# WallLightRemote_V1_0_Power.net
KiCad netlist of a schematic drawn in Altium Designer
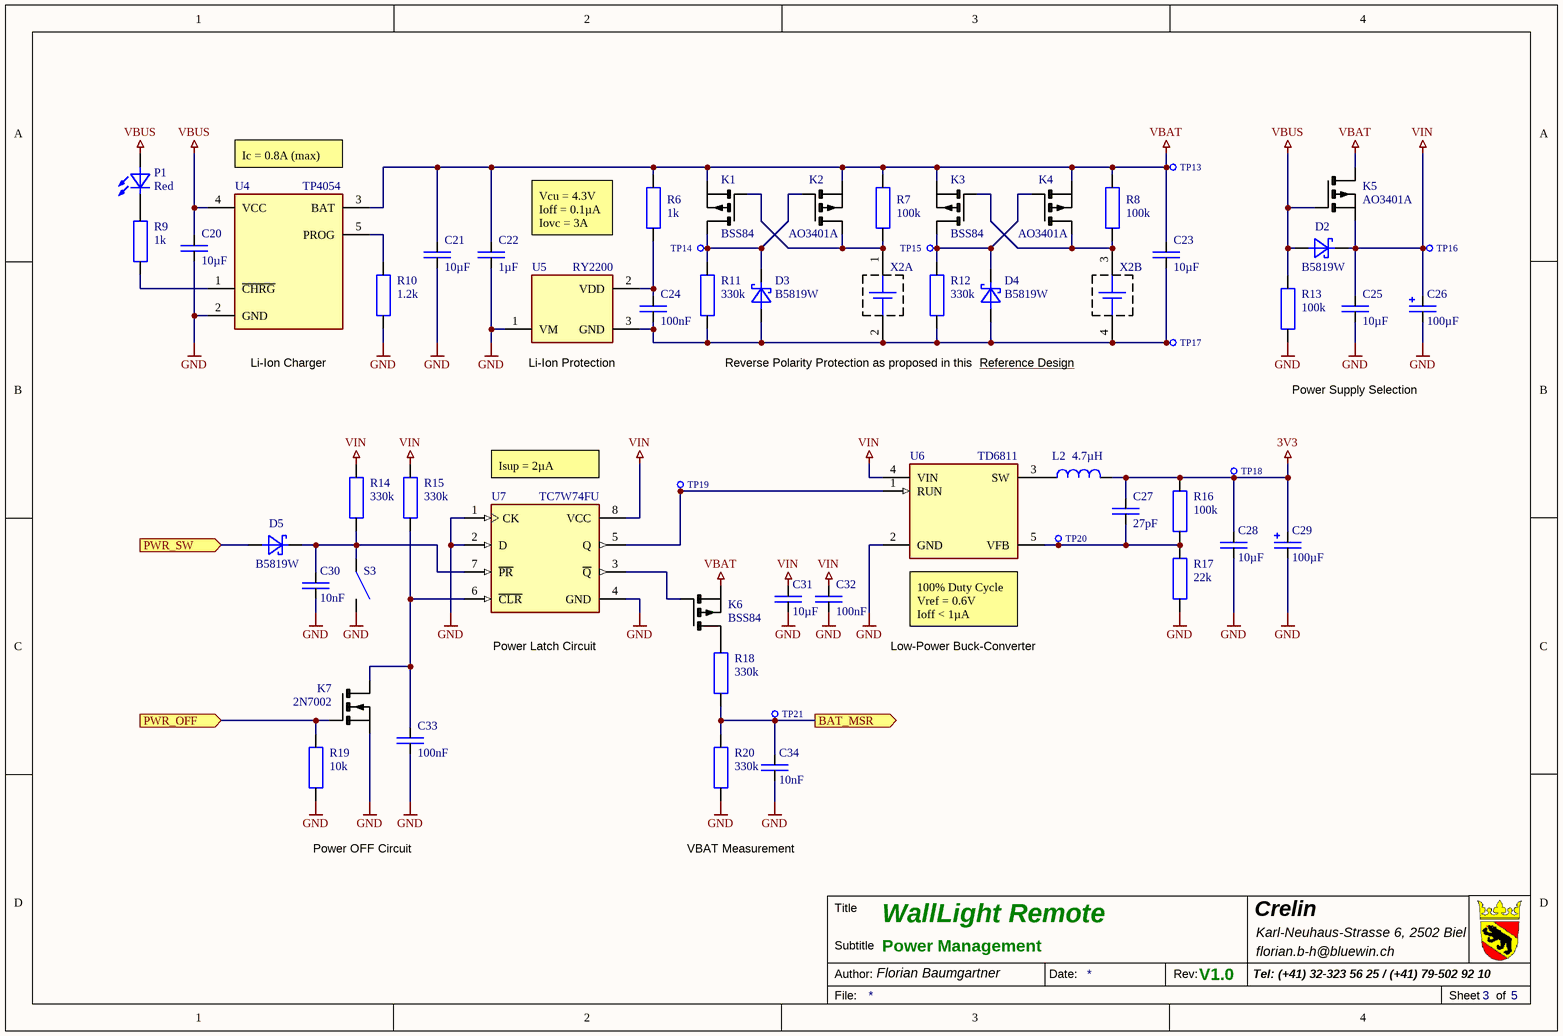
[diagram p0: WallLightRemote_V1.0_Power.SchDoc]

(export (version "E")
  (design (tool "Eeschema 10.0.6"))
  (components
    (comp (ref "C20")
      (value "10µF")
      (footprint "SMD Keramikkondensator 1206")
      (description "SMD Ceramic Capacitor E6")
      (libsource (lib "Ceramic Capacitors-E6") (part "E6 - 10uF"))
    )
    (comp (ref "C21")
      (value "10µF")
      (footprint "SMD Keramikkondensator 1206")
      (description "SMD Ceramic Capacitor E6")
      (libsource (lib "Ceramic Capacitors-E6") (part "E6 - 10uF"))
    )
    (comp (ref "C22")
      (value "1µF")
      (footprint "SMD Keramikkondensator 0603")
      (description "CAP-MK")
      (libsource (lib "AudioAmp") (part "C-CAPACITOR"))
    )
    (comp (ref "C23")
      (value "10µF")
      (footprint "SMD Keramikkondensator 1206")
      (description "SMD Ceramic Capacitor E6")
      (libsource (lib "Ceramic Capacitors-E6") (part "E6 - 10uF"))
    )
    (comp (ref "C24")
      (value "100nF")
      (footprint "SMD Keramikkondensator 0603")
      (description "SMD Ceramic Capacitor E6")
      (libsource (lib "Ceramic Capacitors-E6") (part "E6 - 100nF"))
    )
    (comp (ref "C25")
      (value "10µF")
      (footprint "SMD Keramikkondensator 1206")
      (description "SMD Ceramic Capacitor E6")
      (libsource (lib "Ceramic Capacitors-E6") (part "E6 - 10uF"))
    )
    (comp (ref "C26")
      (value "100µF")
      (footprint "SMD Tantalkondensator 1210 +")
      (description "CAP-Elko")
      (libsource (lib "TFS Integrated Library") (part "C-ELCAP"))
    )
    (comp (ref "C27")
      (value "27pF")
      (footprint "SMD Keramikkondensator 0603")
      (description "CAP-MK")
      (libsource (lib "AudioAmp") (part "C-CAPACITOR"))
    )
    (comp (ref "C28")
      (value "10µF")
      (footprint "SMD Keramikkondensator 1206")
      (description "CAP-MK")
      (libsource (lib "AudioAmp") (part "C-CAPACITOR"))
    )
    (comp (ref "C29")
      (value "100µF")
      (footprint "SMD Tantalkondensator 1210 +")
      (description "CAP-Elko")
      (libsource (lib "TFS Integrated Library") (part "C-ELCAP"))
    )
    (comp (ref "C30")
      (value "10nF")
      (footprint "SMD Keramikkondensator 0603")
      (description "CAP-MK")
      (libsource (lib "AudioAmp") (part "C-CAPACITOR"))
    )
    (comp (ref "C31")
      (value "10µF")
      (footprint "SMD Keramikkondensator 1206")
      (description "CAP-MK")
      (libsource (lib "AudioAmp") (part "C-CAPACITOR"))
    )
    (comp (ref "C32")
      (value "100nF")
      (footprint "SMD Keramikkondensator 0603")
      (description "SMD Ceramic Capacitor E6")
      (libsource (lib "Ceramic Capacitors-E6") (part "E6 - 100nF"))
    )
    (comp (ref "C33")
      (value "100nF")
      (footprint "SMD Keramikkondensator 0603")
      (description "SMD Ceramic Capacitor E6")
      (libsource (lib "Ceramic Capacitors-E6") (part "E6 - 100nF"))
    )
    (comp (ref "C34")
      (value "10nF")
      (footprint "SMD Keramikkondensator 0603")
      (description "CAP-MK")
      (libsource (lib "AudioAmp") (part "C-CAPACITOR"))
    )
    (comp (ref "D2")
      (value "B5819W")
      (footprint "SMD Diode SOD-123")
      (description "S-DIODE")
      (libsource (lib "TFS Integrated Library") (part "R-DIODE{colon}SCHKY"))
    )
    (comp (ref "D3")
      (value "B5819W")
      (footprint "SMD Diode SOD-123")
      (description "S-DIODE")
      (libsource (lib "TFS Integrated Library") (part "R-DIODE{colon}SCHKY"))
    )
    (comp (ref "D4")
      (value "B5819W")
      (footprint "SMD Diode SOD-123")
      (description "S-DIODE")
      (libsource (lib "TFS Integrated Library") (part "R-DIODE{colon}SCHKY"))
    )
    (comp (ref "D5")
      (value "B5819W")
      (footprint "SMD Diode SOD-123")
      (description "S-DIODE")
      (libsource (lib "TFS Integrated Library") (part "R-DIODE{colon}SCHKY"))
    )
    (comp (ref "K1")
      (value "BSS84")
      (footprint "SMD MOSFET SOT-23")
      (description "MOSFET P-Channel")
      (libsource (lib "") (part "K-FET{colon}PIGE_2"))
    )
    (comp (ref "K2")
      (value "AO3401A")
      (footprint "SMD MOSFET SOT-23")
      (description "MOSFET P-Channel")
      (libsource (lib "VLD-Monitor_V1.0") (part "K-FET{colon}PIGE"))
    )
    (comp (ref "K3")
      (value "BSS84")
      (footprint "SMD MOSFET SOT-23")
      (description "MOSFET P-Channel")
      (libsource (lib "") (part "K-FET{colon}PIGE_2"))
    )
    (comp (ref "K4")
      (value "AO3401A")
      (footprint "SMD MOSFET SOT-23")
      (description "MOSFET P-Channel")
      (libsource (lib "VLD-Monitor_V1.0") (part "K-FET{colon}PIGE"))
    )
    (comp (ref "K5")
      (value "AO3401A")
      (footprint "SMD MOSFET SOT-23")
      (description "MOSFET P-Channel")
      (libsource (lib "") (part "K-FET{colon}PIGE_1"))
    )
    (comp (ref "K6")
      (value "BSS84")
      (footprint "SMD MOSFET SOT-23")
      (description "MOSFET P-Channel")
      (libsource (lib "VLD-Monitor_V1.0") (part "K-FET{colon}PIGE"))
    )
    (comp (ref "K7")
      (value "2N7002")
      (footprint "SMD MOSFET SOT-23")
      (description "MOSFET N-Channel")
      (libsource (lib "Nixie-Test") (part "K-FET{colon}NIGE"))
    )
    (comp (ref "L2")
      (value "4.7µH")
      (footprint "SMD Inductor 3.2x2.5x1.7")
      (description "Shielded Power Inductor")
      (libsource (lib "Nixie-Test") (part "L-COIL"))
    )
    (comp (ref "P1")
      (value "Red")
      (footprint "SMD LED 0603")
      (description "LED (als Lampe E / alt H)")
      (libsource (lib "TFS Integrated Library") (part "P-LED"))
    )
    (comp (ref "R6")
      (value "1k")
      (footprint "SMD Widerstand 0603")
      (description "RES (E=Heizwiderstand B=Messwandler)")
      (libsource (lib "") (part "R-RESISTOR_1"))
    )
    (comp (ref "R7")
      (value "100k")
      (footprint "SMD Widerstand 0603")
      (description "RES (E=Heizwiderstand B=Messwandler)")
      (libsource (lib "TFS Integrated Library") (part "R-RESISTOR"))
    )
    (comp (ref "R8")
      (value "100k")
      (footprint "SMD Widerstand 0603")
      (description "RES (E=Heizwiderstand B=Messwandler)")
      (libsource (lib "TFS Integrated Library") (part "R-RESISTOR"))
    )
    (comp (ref "R9")
      (value "1k")
      (footprint "SMD Widerstand 0603")
      (description "RES (E=Heizwiderstand B=Messwandler)")
      (libsource (lib "") (part "R-RESISTOR_2"))
    )
    (comp (ref "R10")
      (value "1.2k")
      (footprint "SMD Widerstand 0603")
      (description "RES (E=Heizwiderstand B=Messwandler)")
      (libsource (lib "TFS Integrated Library") (part "R-RESISTOR"))
    )
    (comp (ref "R11")
      (value "330k")
      (footprint "SMD Widerstand 0603")
      (description "RES (E=Heizwiderstand B=Messwandler)")
      (libsource (lib "TFS Integrated Library") (part "R-RESISTOR"))
    )
    (comp (ref "R12")
      (value "330k")
      (footprint "SMD Widerstand 0603")
      (description "RES (E=Heizwiderstand B=Messwandler)")
      (libsource (lib "TFS Integrated Library") (part "R-RESISTOR"))
    )
    (comp (ref "R13")
      (value "100k")
      (footprint "SMD Widerstand 0603")
      (description "RES (E=Heizwiderstand B=Messwandler)")
      (libsource (lib "TFS Integrated Library") (part "R-RESISTOR"))
    )
    (comp (ref "R14")
      (value "330k")
      (footprint "SMD Widerstand 0603")
      (description "RES (E=Heizwiderstand B=Messwandler)")
      (libsource (lib "TFS Integrated Library") (part "R-RESISTOR"))
    )
    (comp (ref "R15")
      (value "330k")
      (footprint "SMD Widerstand 0603")
      (description "RES (E=Heizwiderstand B=Messwandler)")
      (libsource (lib "TFS Integrated Library") (part "R-RESISTOR"))
    )
    (comp (ref "R16")
      (value "100k")
      (footprint "SMD Widerstand 0603")
      (description "RES (E=Heizwiderstand B=Messwandler)")
      (libsource (lib "TFS Integrated Library") (part "R-RESISTOR"))
    )
    (comp (ref "R17")
      (value "22k")
      (footprint "SMD Widerstand 0603")
      (description "RES (E=Heizwiderstand B=Messwandler)")
      (libsource (lib "") (part "R-RESISTOR_1"))
    )
    (comp (ref "R18")
      (value "330k")
      (footprint "SMD Widerstand 0603")
      (description "RES (E=Heizwiderstand B=Messwandler)")
      (libsource (lib "TFS Integrated Library") (part "R-RESISTOR"))
    )
    (comp (ref "R19")
      (value "10k")
      (footprint "SMD Widerstand 0603")
      (description "RES (E=Heizwiderstand B=Messwandler)")
      (libsource (lib "") (part "R-RESISTOR_1"))
    )
    (comp (ref "R20")
      (value "330k")
      (footprint "SMD Widerstand 0603")
      (description "RES (E=Heizwiderstand B=Messwandler)")
      (libsource (lib "TFS Integrated Library") (part "R-RESISTOR"))
    )
    (comp (ref "S3")
      (value "SMD-Button")
      (footprint "SMD Button 6.5x6.0x2.5")
      (description "Button SPST")
      (libsource (lib "Switches") (part "Button 3mmx2.5mm"))
    )
    (comp (ref "TP13")
      (value "X-TP")
      (footprint "SMD Testpunkt Ø1mm")
      (description "Testpunkt")
      (libsource (lib "VLD-Monitor_V1.0") (part "X-TP"))
    )
    (comp (ref "TP14")
      (value "X-TP")
      (footprint "SMD Testpunkt Ø1mm")
      (description "Testpunkt")
      (libsource (lib "VLD-Monitor_V1.0") (part "X-TP"))
    )
    (comp (ref "TP15")
      (value "X-TP")
      (footprint "SMD Testpunkt Ø1mm")
      (description "Testpunkt")
      (libsource (lib "VLD-Monitor_V1.0") (part "X-TP"))
    )
    (comp (ref "TP16")
      (value "X-TP")
      (footprint "SMD Testpunkt Ø1mm")
      (description "Testpunkt")
      (libsource (lib "VLD-Monitor_V1.0") (part "X-TP"))
    )
    (comp (ref "TP17")
      (value "X-TP")
      (footprint "SMD Testpunkt Ø1mm")
      (description "Testpunkt")
      (libsource (lib "VLD-Monitor_V1.0") (part "X-TP"))
    )
    (comp (ref "TP18")
      (value "X-TP")
      (footprint "SMD Testpunkt Ø1mm")
      (description "Testpunkt")
      (libsource (lib "VLD-Monitor_V1.0") (part "X-TP"))
    )
    (comp (ref "TP19")
      (value "X-TP")
      (footprint "SMD Testpunkt Ø1mm")
      (description "Testpunkt")
      (libsource (lib "VLD-Monitor_V1.0") (part "X-TP"))
    )
    (comp (ref "TP20")
      (value "X-TP")
      (footprint "SMD Testpunkt Ø1mm")
      (description "Testpunkt")
      (libsource (lib "VLD-Monitor_V1.0") (part "X-TP"))
    )
    (comp (ref "TP21")
      (value "X-TP")
      (footprint "SMD Testpunkt Ø1mm")
      (description "Testpunkt")
      (libsource (lib "VLD-Monitor_V1.0") (part "X-TP"))
    )
    (comp (ref "U4")
      (value "TP4054")
      (footprint "SMD IC SOT-23-5")
      (description "Standalone Linear Li-Ion Battery Charger")
      (libsource (lib "Velotour_2022") (part "U-TP4054"))
    )
    (comp (ref "U5")
      (value "RY2200")
      (footprint "SMD IC SOT-23-3")
      (description "One Cell Li-ion and Li-poly Battery Protection IC")
      (libsource (lib "Velotour_2022") (part "U-RY2200"))
    )
    (comp (ref "U6")
      (value "TD6811")
      (footprint "SMD IC SOT-23-5")
      (description "1.5MHz 1.2A Synchronous Step-Down Converter")
      (libsource (lib "Velotour_2022") (part "U-TD6811"))
    )
    (comp (ref "U7")
      (value "TC7W74FU")
      (footprint "SMD IC TSSOP-8")
      (description "Low-Power D-Flip-Flop with Preset & Clear")
      (libsource (lib "Velotour_2022") (part "U-TC7W74FU"))
    )
    (comp (ref "X2")
      (value "18650 Dual Battery Holder")
      (footprint "SMD Battery-Holder (1048P)")
      (libsource (lib "Velotour_2022") (part "X-18650_Dual-Holder"))
    )
  )
  (nets
    (net (code "1") (name "/BAT_MSR") (class "Default")
      (node (ref "C34") (pin "2") (pinfunction "2_2") (pintype "passive"))
      (node (ref "R18") (pin "1") (pinfunction "1_1") (pintype "passive"))
      (node (ref "R20") (pin "2") (pinfunction "2_2") (pintype "passive"))
      (node (ref "TP21") (pin "1") (pinfunction "1_1") (pintype "passive"))
    )
    (net (code "2") (name "/PWR_OFF") (class "Default")
      (node (ref "K7") (pin "G") (pinfunction "G_G") (pintype "passive"))
      (node (ref "R19") (pin "2") (pinfunction "2_2") (pintype "passive"))
    )
    (net (code "3") (name "/PWR_SW") (class "Default")
      (node (ref "D5") (pin "A") (pinfunction "A_A") (pintype "passive"))
    )
    (net (code "4") (name "3V3") (class "Default")
      (node (ref "C27") (pin "1") (pinfunction "1_1") (pintype "passive"))
      (node (ref "C28") (pin "2") (pinfunction "2_2") (pintype "passive"))
      (node (ref "C29") (pin "P") (pinfunction "+_P") (pintype "passive"))
      (node (ref "L2") (pin "2") (pinfunction "2_2") (pintype "passive"))
      (node (ref "R16") (pin "2") (pinfunction "2_2") (pintype "passive"))
      (node (ref "TP18") (pin "1") (pinfunction "1_1") (pintype "passive"))
    )
    (net (code "5") (name "GND") (class "Default")
      (node (ref "C20") (pin "1") (pinfunction "1_1") (pintype "passive"))
      (node (ref "C21") (pin "1") (pinfunction "1_1") (pintype "passive"))
      (node (ref "C22") (pin "1") (pinfunction "1_1") (pintype "passive"))
      (node (ref "C25") (pin "1") (pinfunction "1_1") (pintype "passive"))
      (node (ref "C26") (pin "M") (pinfunction "-_M") (pintype "passive"))
      (node (ref "C28") (pin "1") (pinfunction "1_1") (pintype "passive"))
      (node (ref "C29") (pin "M") (pinfunction "-_M") (pintype "passive"))
      (node (ref "C30") (pin "1") (pinfunction "1_1") (pintype "passive"))
      (node (ref "C31") (pin "1") (pinfunction "1_1") (pintype "passive"))
      (node (ref "C32") (pin "1") (pinfunction "1_1") (pintype "passive"))
      (node (ref "C33") (pin "1") (pinfunction "1_1") (pintype "passive"))
      (node (ref "C34") (pin "1") (pinfunction "1_1") (pintype "passive"))
      (node (ref "K7") (pin "S") (pinfunction "S_S") (pintype "passive"))
      (node (ref "R10") (pin "1") (pinfunction "1_1") (pintype "passive"))
      (node (ref "R13") (pin "1") (pinfunction "1_1") (pintype "passive"))
      (node (ref "R17") (pin "1") (pinfunction "1_1") (pintype "passive"))
      (node (ref "R19") (pin "1") (pinfunction "1_1") (pintype "passive"))
      (node (ref "R20") (pin "1") (pinfunction "1_1") (pintype "passive"))
      (node (ref "S3") (pin "2") (pinfunction "2_2") (pintype "passive"))
      (node (ref "U4") (pin "2") (pinfunction "GND_2") (pintype "power_in"))
      (node (ref "U5") (pin "1") (pinfunction "VM_1") (pintype "power_in"))
      (node (ref "U6") (pin "2") (pinfunction "GND_2") (pintype "power_in"))
      (node (ref "U7") (pin "1") (pinfunction "CK_1") (pintype "input"))
      (node (ref "U7") (pin "2") (pinfunction "D_2") (pintype "input"))
      (node (ref "U7") (pin "4") (pinfunction "GND_4") (pintype "power_in"))
    )
    (net (code "6") (name "Net-(D3-PadK)") (class "Default")
      (node (ref "D3") (pin "K") (pinfunction "K_K") (pintype "passive"))
      (node (ref "K1") (pin "D") (pinfunction "D_D") (pintype "passive"))
      (node (ref "K2") (pin "G") (pinfunction "G_G") (pintype "passive"))
      (node (ref "R11") (pin "2") (pinfunction "2_2") (pintype "passive"))
      (node (ref "TP14") (pin "1") (pinfunction "1_1") (pintype "passive"))
    )
    (net (code "7") (name "Net-(D4-PadK)") (class "Default")
      (node (ref "D4") (pin "K") (pinfunction "K_K") (pintype "passive"))
      (node (ref "K3") (pin "D") (pinfunction "D_D") (pintype "passive"))
      (node (ref "K4") (pin "G") (pinfunction "G_G") (pintype "passive"))
      (node (ref "R12") (pin "2") (pinfunction "2_2") (pintype "passive"))
      (node (ref "TP15") (pin "1") (pinfunction "1_1") (pintype "passive"))
    )
    (net (code "8") (name "Net-(K6-PadD)") (class "Default")
      (node (ref "K6") (pin "D") (pinfunction "D_D") (pintype "passive"))
      (node (ref "R18") (pin "2") (pinfunction "2_2") (pintype "passive"))
    )
    (net (code "9") (name "Net-(P1-PadK)") (class "Default")
      (node (ref "P1") (pin "K") (pinfunction "K_K") (pintype "passive"))
      (node (ref "R9") (pin "1") (pinfunction "1_1") (pintype "passive"))
    )
    (net (code "10") (name "Net-(U4-PROG)") (class "Default")
      (node (ref "R10") (pin "2") (pinfunction "2_2") (pintype "passive"))
      (node (ref "U4") (pin "5") (pinfunction "PROG_5") (pintype "passive"))
    )
    (net (code "11") (name "Net-(U4-~{CHRG})") (class "Default")
      (node (ref "R9") (pin "2") (pinfunction "2_2") (pintype "passive"))
      (node (ref "U4") (pin "1") (pinfunction "~{CHRG}_1") (pintype "open_collector"))
    )
    (net (code "12") (name "Net-(U5-GND)") (class "Default")
      (node (ref "C23") (pin "1") (pinfunction "1_1") (pintype "passive"))
      (node (ref "C24") (pin "1") (pinfunction "1_1") (pintype "passive"))
      (node (ref "D3") (pin "A") (pinfunction "A_A") (pintype "passive"))
      (node (ref "D4") (pin "A") (pinfunction "A_A") (pintype "passive"))
      (node (ref "R11") (pin "1") (pinfunction "1_1") (pintype "passive"))
      (node (ref "R12") (pin "1") (pinfunction "1_1") (pintype "passive"))
      (node (ref "TP17") (pin "1") (pinfunction "1_1") (pintype "passive"))
      (node (ref "U5") (pin "3") (pinfunction "GND_3") (pintype "power_in"))
      (node (ref "X2") (pin "2") (pinfunction "B1N_2") (pintype "passive"))
      (node (ref "X2") (pin "4") (pinfunction "B2N_4") (pintype "passive"))
    )
    (net (code "13") (name "Net-(U5-VDD)") (class "Default")
      (node (ref "C24") (pin "2") (pinfunction "2_2") (pintype "passive"))
      (node (ref "R6") (pin "1") (pinfunction "1_1") (pintype "passive"))
      (node (ref "U5") (pin "2") (pinfunction "VDD_2") (pintype "power_in"))
    )
    (net (code "14") (name "Net-(U6-RUN)") (class "Default")
      (node (ref "TP19") (pin "1") (pinfunction "1_1") (pintype "passive"))
      (node (ref "U6") (pin "1") (pinfunction "RUN_1") (pintype "input"))
      (node (ref "U7") (pin "5") (pinfunction "Q_5") (pintype "output"))
    )
    (net (code "15") (name "Net-(U6-SW)") (class "Default")
      (node (ref "L2") (pin "1") (pinfunction "1_1") (pintype "passive"))
      (node (ref "U6") (pin "3") (pinfunction "SW_3") (pintype "passive"))
    )
    (net (code "16") (name "Net-(U6-VFB)") (class "Default")
      (node (ref "C27") (pin "2") (pinfunction "2_2") (pintype "passive"))
      (node (ref "R16") (pin "1") (pinfunction "1_1") (pintype "passive"))
      (node (ref "R17") (pin "2") (pinfunction "2_2") (pintype "passive"))
      (node (ref "TP20") (pin "1") (pinfunction "1_1") (pintype "passive"))
      (node (ref "U6") (pin "5") (pinfunction "VFB_5") (pintype "passive"))
    )
    (net (code "17") (name "Net-(U7-~{CLR})") (class "Default")
      (node (ref "C33") (pin "2") (pinfunction "2_2") (pintype "passive"))
      (node (ref "K7") (pin "D") (pinfunction "D_D") (pintype "passive"))
      (node (ref "R15") (pin "1") (pinfunction "1_1") (pintype "passive"))
      (node (ref "U7") (pin "6") (pinfunction "~{CLR}_6") (pintype "input"))
    )
    (net (code "18") (name "Net-(U7-~{PR})") (class "Default")
      (node (ref "C30") (pin "2") (pinfunction "2_2") (pintype "passive"))
      (node (ref "D5") (pin "K") (pinfunction "K_K") (pintype "passive"))
      (node (ref "R14") (pin "1") (pinfunction "1_1") (pintype "passive"))
      (node (ref "S3") (pin "1") (pinfunction "1_1") (pintype "passive"))
      (node (ref "U7") (pin "7") (pinfunction "~{PR}_7") (pintype "input"))
    )
    (net (code "19") (name "Net-(U7-~{Q})") (class "Default")
      (node (ref "K6") (pin "G") (pinfunction "G_G") (pintype "passive"))
      (node (ref "U7") (pin "3") (pinfunction "~{Q}_3") (pintype "output"))
    )
    (net (code "20") (name "Net-(X2A-B1P)") (class "Default")
      (node (ref "K1") (pin "G") (pinfunction "G_G") (pintype "passive"))
      (node (ref "K2") (pin "D") (pinfunction "D_D") (pintype "passive"))
      (node (ref "R7") (pin "1") (pinfunction "1_1") (pintype "passive"))
      (node (ref "X2") (pin "1") (pinfunction "B1P_1") (pintype "passive"))
    )
    (net (code "21") (name "Net-(X2B-B2P)") (class "Default")
      (node (ref "K3") (pin "G") (pinfunction "G_G") (pintype "passive"))
      (node (ref "K4") (pin "D") (pinfunction "D_D") (pintype "passive"))
      (node (ref "R8") (pin "1") (pinfunction "1_1") (pintype "passive"))
      (node (ref "X2") (pin "3") (pinfunction "B2P_3") (pintype "passive"))
    )
    (net (code "22") (name "VBAT") (class "Default")
      (node (ref "C21") (pin "2") (pinfunction "2_2") (pintype "passive"))
      (node (ref "C22") (pin "2") (pinfunction "2_2") (pintype "passive"))
      (node (ref "C23") (pin "2") (pinfunction "2_2") (pintype "passive"))
      (node (ref "K1") (pin "S") (pinfunction "S_S") (pintype "passive"))
      (node (ref "K2") (pin "S") (pinfunction "S_S") (pintype "passive"))
      (node (ref "K3") (pin "S") (pinfunction "S_S") (pintype "passive"))
      (node (ref "K4") (pin "S") (pinfunction "S_S") (pintype "passive"))
      (node (ref "K5") (pin "D") (pinfunction "D_D") (pintype "passive"))
      (node (ref "K6") (pin "S") (pinfunction "S_S") (pintype "passive"))
      (node (ref "R6") (pin "2") (pinfunction "2_2") (pintype "passive"))
      (node (ref "R7") (pin "2") (pinfunction "2_2") (pintype "passive"))
      (node (ref "R8") (pin "2") (pinfunction "2_2") (pintype "passive"))
      (node (ref "TP13") (pin "1") (pinfunction "1_1") (pintype "passive"))
      (node (ref "U4") (pin "3") (pinfunction "BAT_3") (pintype "passive"))
    )
    (net (code "23") (name "VBUS") (class "Default")
      (node (ref "C20") (pin "2") (pinfunction "2_2") (pintype "passive"))
      (node (ref "D2") (pin "A") (pinfunction "A_A") (pintype "passive"))
      (node (ref "K5") (pin "G") (pinfunction "G_G") (pintype "passive"))
      (node (ref "P1") (pin "A") (pinfunction "A_A") (pintype "passive"))
      (node (ref "R13") (pin "2") (pinfunction "2_2") (pintype "passive"))
      (node (ref "U4") (pin "4") (pinfunction "VCC_4") (pintype "power_in"))
    )
    (net (code "24") (name "VIN") (class "Default")
      (node (ref "C25") (pin "2") (pinfunction "2_2") (pintype "passive"))
      (node (ref "C26") (pin "P") (pinfunction "+_P") (pintype "passive"))
      (node (ref "C31") (pin "2") (pinfunction "2_2") (pintype "passive"))
      (node (ref "C32") (pin "2") (pinfunction "2_2") (pintype "passive"))
      (node (ref "D2") (pin "K") (pinfunction "K_K") (pintype "passive"))
      (node (ref "K5") (pin "S") (pinfunction "S_S") (pintype "passive"))
      (node (ref "R14") (pin "2") (pinfunction "2_2") (pintype "passive"))
      (node (ref "R15") (pin "2") (pinfunction "2_2") (pintype "passive"))
      (node (ref "TP16") (pin "1") (pinfunction "1_1") (pintype "passive"))
      (node (ref "U6") (pin "4") (pinfunction "VIN_4") (pintype "power_in"))
      (node (ref "U7") (pin "8") (pinfunction "VCC_8") (pintype "power_in"))
    )
  )
)
